# EggMill.net
KiCad netlist of a schematic drawn in EAGLE
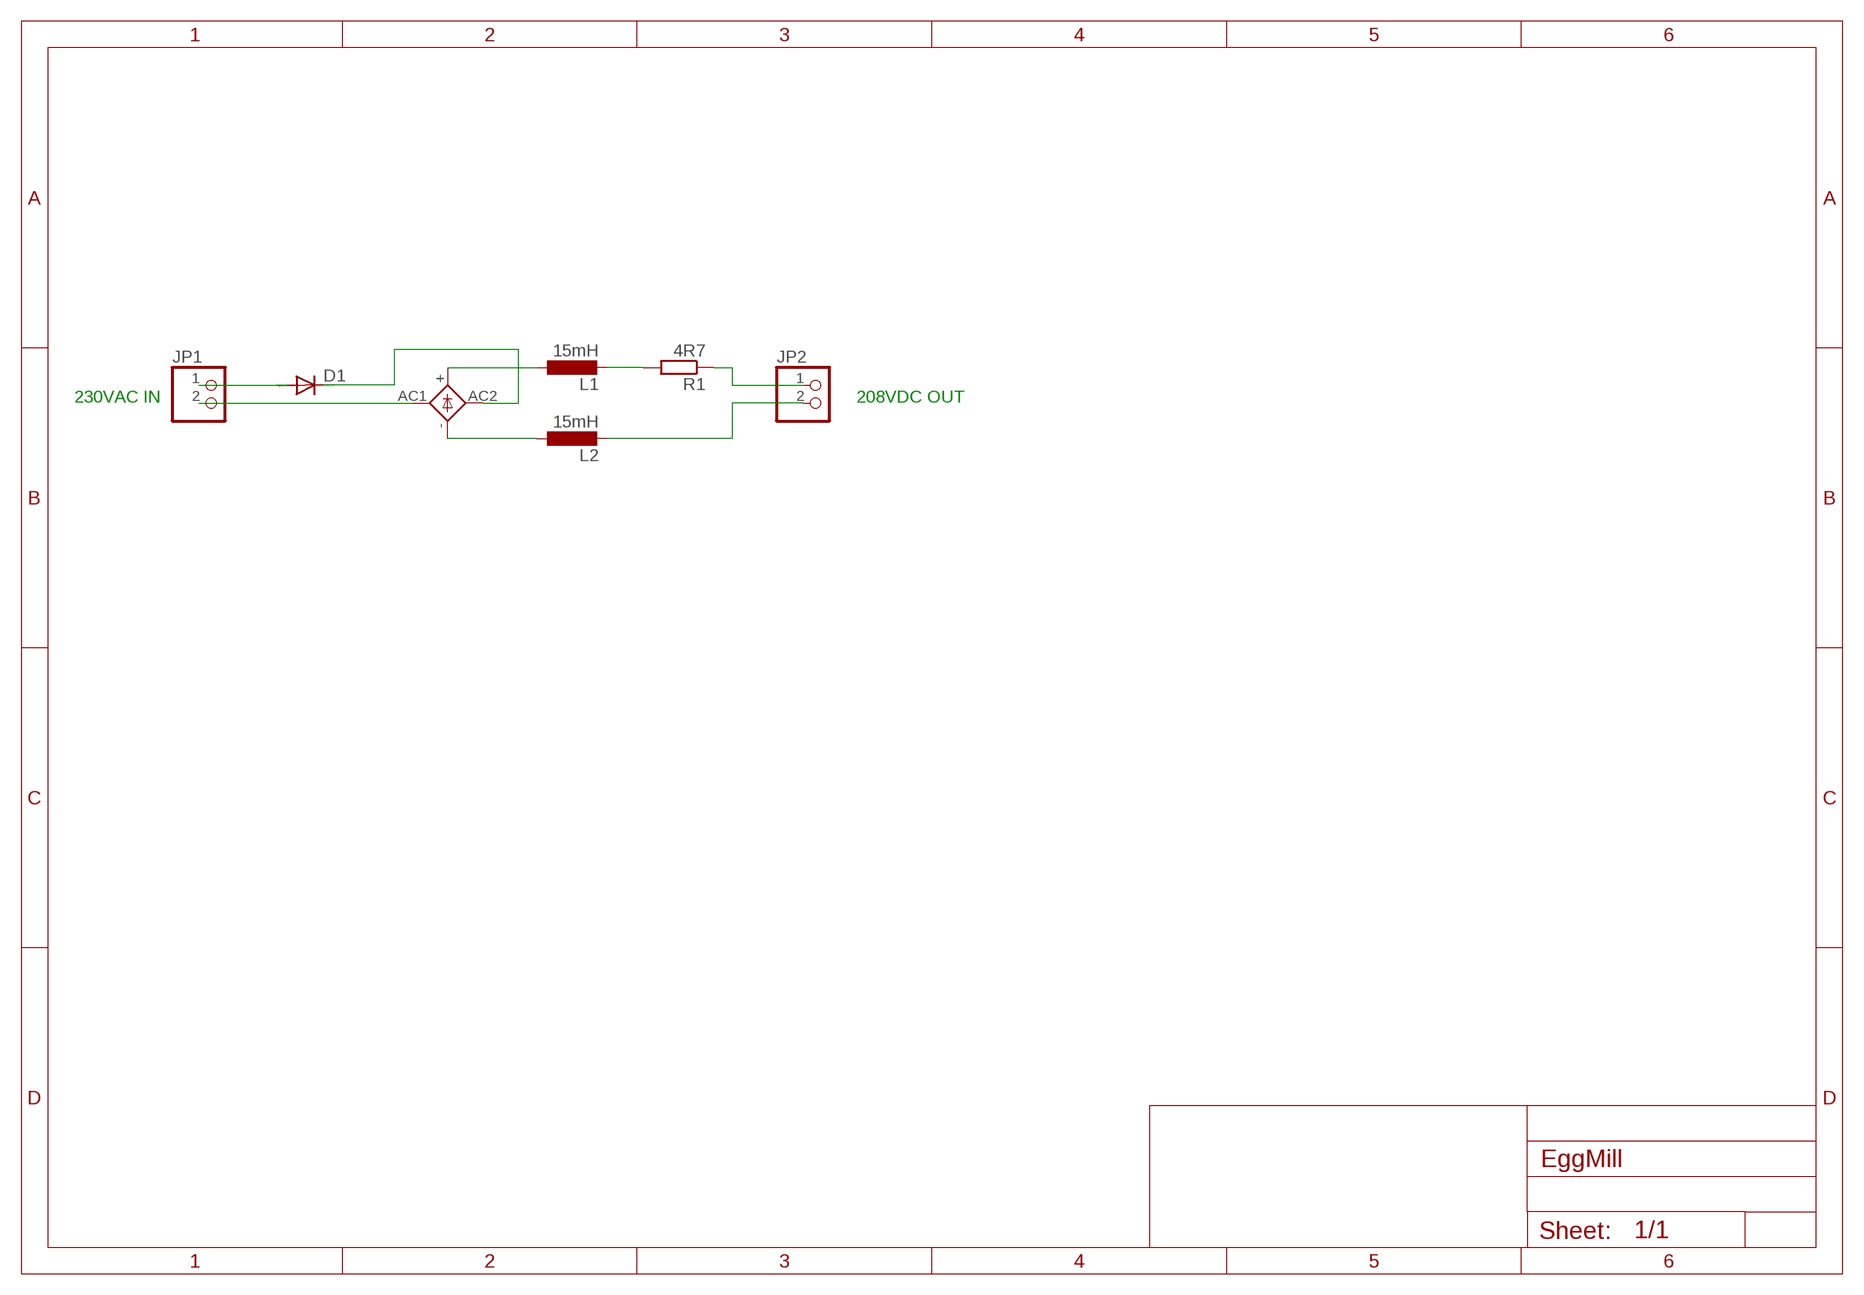
[diagram p0: schematic, sheet 1]

(export (version "E")
  (design (tool "Eeschema 10.0.6"))
  (components
    (comp (ref "B1")
      (value "DSI32")
      (footprint "eagle-import:DSI32")
      (libsource (lib "eagle-import") (part "DSI32"))
    )
    (comp (ref "D1")
      (value "BY505")
      (footprint "eagle-import:SOD61A")
      (libsource (lib "eagle-import") (part "BY505"))
    )
    (comp (ref "JP1")
      (value "PINHD-1X2")
      (footprint "eagle-import:1X02")
      (libsource (lib "eagle-import") (part "PINHD-1X2"))
    )
    (comp (ref "JP2")
      (value "PINHD-1X2")
      (footprint "eagle-import:1X02")
      (libsource (lib "eagle-import") (part "PINHD-1X2"))
    )
    (comp (ref "L1")
      (value "15mH")
      (footprint "eagle-import:LAL03KH")
      (libsource (lib "eagle-import") (part "L-EULAL03KB"))
    )
    (comp (ref "L2")
      (value "15mH")
      (footprint "eagle-import:LAL03KH")
      (libsource (lib "eagle-import") (part "L-EULAL03KB"))
    )
    (comp (ref "R1")
      (value "4R7")
      (footprint "eagle-import:0922V")
      (libsource (lib "eagle-import") (part "R-EU_0922V"))
    )
  )
  (nets
    (net (code "1") (name "Net-(B1-Pad+)") (class "Default")
      (node (ref "B1") (pin "+") (pinfunction "+_+") (pintype "passive"))
      (node (ref "L1") (pin "1") (pinfunction "1_1") (pintype "passive"))
    )
    (net (code "2") (name "Net-(B1-Pad-)") (class "Default")
      (node (ref "B1") (pin "-") (pinfunction "-_-") (pintype "passive"))
      (node (ref "L2") (pin "1") (pinfunction "1_1") (pintype "passive"))
    )
    (net (code "3") (name "Net-(B1-PadAC1)") (class "Default")
      (node (ref "B1") (pin "AC1") (pinfunction "AC1_AC1") (pintype "passive"))
      (node (ref "JP1") (pin "2") (pinfunction "2_2") (pintype "passive"))
    )
    (net (code "4") (name "Net-(B1-PadAC2)") (class "Default")
      (node (ref "B1") (pin "AC2") (pinfunction "AC2_AC2") (pintype "passive"))
      (node (ref "D1") (pin "C") (pinfunction "C_C") (pintype "passive"))
    )
    (net (code "5") (name "Net-(D1-PadA)") (class "Default")
      (node (ref "D1") (pin "A") (pinfunction "A_A") (pintype "passive"))
      (node (ref "JP1") (pin "1") (pinfunction "1_1") (pintype "passive"))
    )
    (net (code "6") (name "Net-(JP2-Pad1)") (class "Default")
      (node (ref "JP2") (pin "1") (pinfunction "1_1") (pintype "passive"))
      (node (ref "R1") (pin "1") (pinfunction "1_1") (pintype "passive"))
    )
    (net (code "7") (name "Net-(JP2-Pad2)") (class "Default")
      (node (ref "JP2") (pin "2") (pinfunction "2_2") (pintype "passive"))
      (node (ref "L2") (pin "2") (pinfunction "2_2") (pintype "passive"))
    )
    (net (code "8") (name "Net-(L1-Pad2)") (class "Default")
      (node (ref "L1") (pin "2") (pinfunction "2_2") (pintype "passive"))
      (node (ref "R1") (pin "2") (pinfunction "2_2") (pintype "passive"))
    )
  )
)
